# ledpanel-001.net
KiCad netlist of a schematic drawn in EAGLE
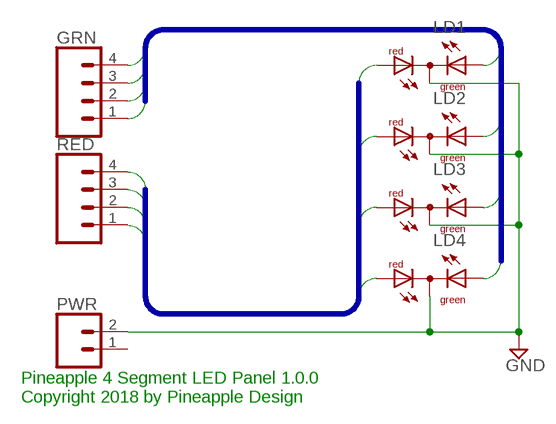
[diagram p0: schematic, sheet 1]

(export (version "E")
  (design (tool "Eeschema 10.0.6"))
  (components
    (comp (ref "GRN")
      (value "CONN_04JST-PTH-VERT")
      (footprint "eagle-import:JST-4-PTH-VERT")
      (libsource (lib "eagle-import") (part "CONN_04JST-PTH-VERT"))
    )
    (comp (ref "LD1")
      (value "DUOLED-RG-C")
      (footprint "eagle-import:DUOLED-C-5MM")
      (libsource (lib "eagle-import") (part "DUOLED-RG-C"))
    )
    (comp (ref "LD2")
      (value "DUOLED-RG-C")
      (footprint "eagle-import:DUOLED-C-5MM")
      (libsource (lib "eagle-import") (part "DUOLED-RG-C"))
    )
    (comp (ref "LD3")
      (value "DUOLED-RG-C")
      (footprint "eagle-import:DUOLED-C-5MM")
      (libsource (lib "eagle-import") (part "DUOLED-RG-C"))
    )
    (comp (ref "LD4")
      (value "DUOLED-RG-C")
      (footprint "eagle-import:DUOLED-C-5MM")
      (libsource (lib "eagle-import") (part "DUOLED-RG-C"))
    )
    (comp (ref "PWR")
      (value "CONN_02-JST-2-PTH-NO_SILK")
      (footprint "eagle-import:JST-2-PTH-NS")
      (libsource (lib "eagle-import") (part "CONN_02-JST-2-PTH-NO_SILK"))
    )
    (comp (ref "RED")
      (value "CONN_04JST-PTH-VERT")
      (footprint "eagle-import:JST-4-PTH-VERT")
      (libsource (lib "eagle-import") (part "CONN_04JST-PTH-VERT"))
    )
  )
  (nets
    (net (code "1") (name "/GREEN1") (class "Default")
      (node (ref "GRN") (pin "1") (pinfunction "1_1") (pintype "passive"))
      (node (ref "LD4") (pin "AX") (pinfunction "AG_AX") (pintype "passive"))
    )
    (net (code "2") (name "/GREEN2") (class "Default")
      (node (ref "GRN") (pin "2") (pinfunction "2_2") (pintype "passive"))
      (node (ref "LD3") (pin "AX") (pinfunction "AG_AX") (pintype "passive"))
    )
    (net (code "3") (name "/GREEN3") (class "Default")
      (node (ref "GRN") (pin "3") (pinfunction "3_3") (pintype "passive"))
      (node (ref "LD2") (pin "AX") (pinfunction "AG_AX") (pintype "passive"))
    )
    (net (code "4") (name "/GREEN4") (class "Default")
      (node (ref "GRN") (pin "4") (pinfunction "4_4") (pintype "passive"))
      (node (ref "LD1") (pin "AX") (pinfunction "AG_AX") (pintype "passive"))
    )
    (net (code "5") (name "/RED1") (class "Default")
      (node (ref "LD4") (pin "AR") (pinfunction "AR_AR") (pintype "passive"))
      (node (ref "RED") (pin "1") (pinfunction "1_1") (pintype "passive"))
    )
    (net (code "6") (name "/RED2") (class "Default")
      (node (ref "LD3") (pin "AR") (pinfunction "AR_AR") (pintype "passive"))
      (node (ref "RED") (pin "2") (pinfunction "2_2") (pintype "passive"))
    )
    (net (code "7") (name "/RED3") (class "Default")
      (node (ref "LD2") (pin "AR") (pinfunction "AR_AR") (pintype "passive"))
      (node (ref "RED") (pin "3") (pinfunction "3_3") (pintype "passive"))
    )
    (net (code "8") (name "/RED4") (class "Default")
      (node (ref "LD1") (pin "AR") (pinfunction "AR_AR") (pintype "passive"))
      (node (ref "RED") (pin "4") (pinfunction "4_4") (pintype "passive"))
    )
    (net (code "9") (name "GND") (class "Default")
      (node (ref "LD1") (pin "C") (pinfunction "C_C") (pintype "passive"))
      (node (ref "LD2") (pin "C") (pinfunction "C_C") (pintype "passive"))
      (node (ref "LD3") (pin "C") (pinfunction "C_C") (pintype "passive"))
      (node (ref "LD4") (pin "C") (pinfunction "C_C") (pintype "passive"))
      (node (ref "PWR") (pin "2") (pinfunction "2_2") (pintype "passive"))
    )
    (net (code "10") (name "unconnected-(PWR-Pad1)") (class "Default")
      (node (ref "PWR") (pin "1") (pinfunction "1_1") (pintype "passive"))
    )
  )
)
